# 05_Ethernet.net
KiCad netlist of a schematic drawn in Altium Designer
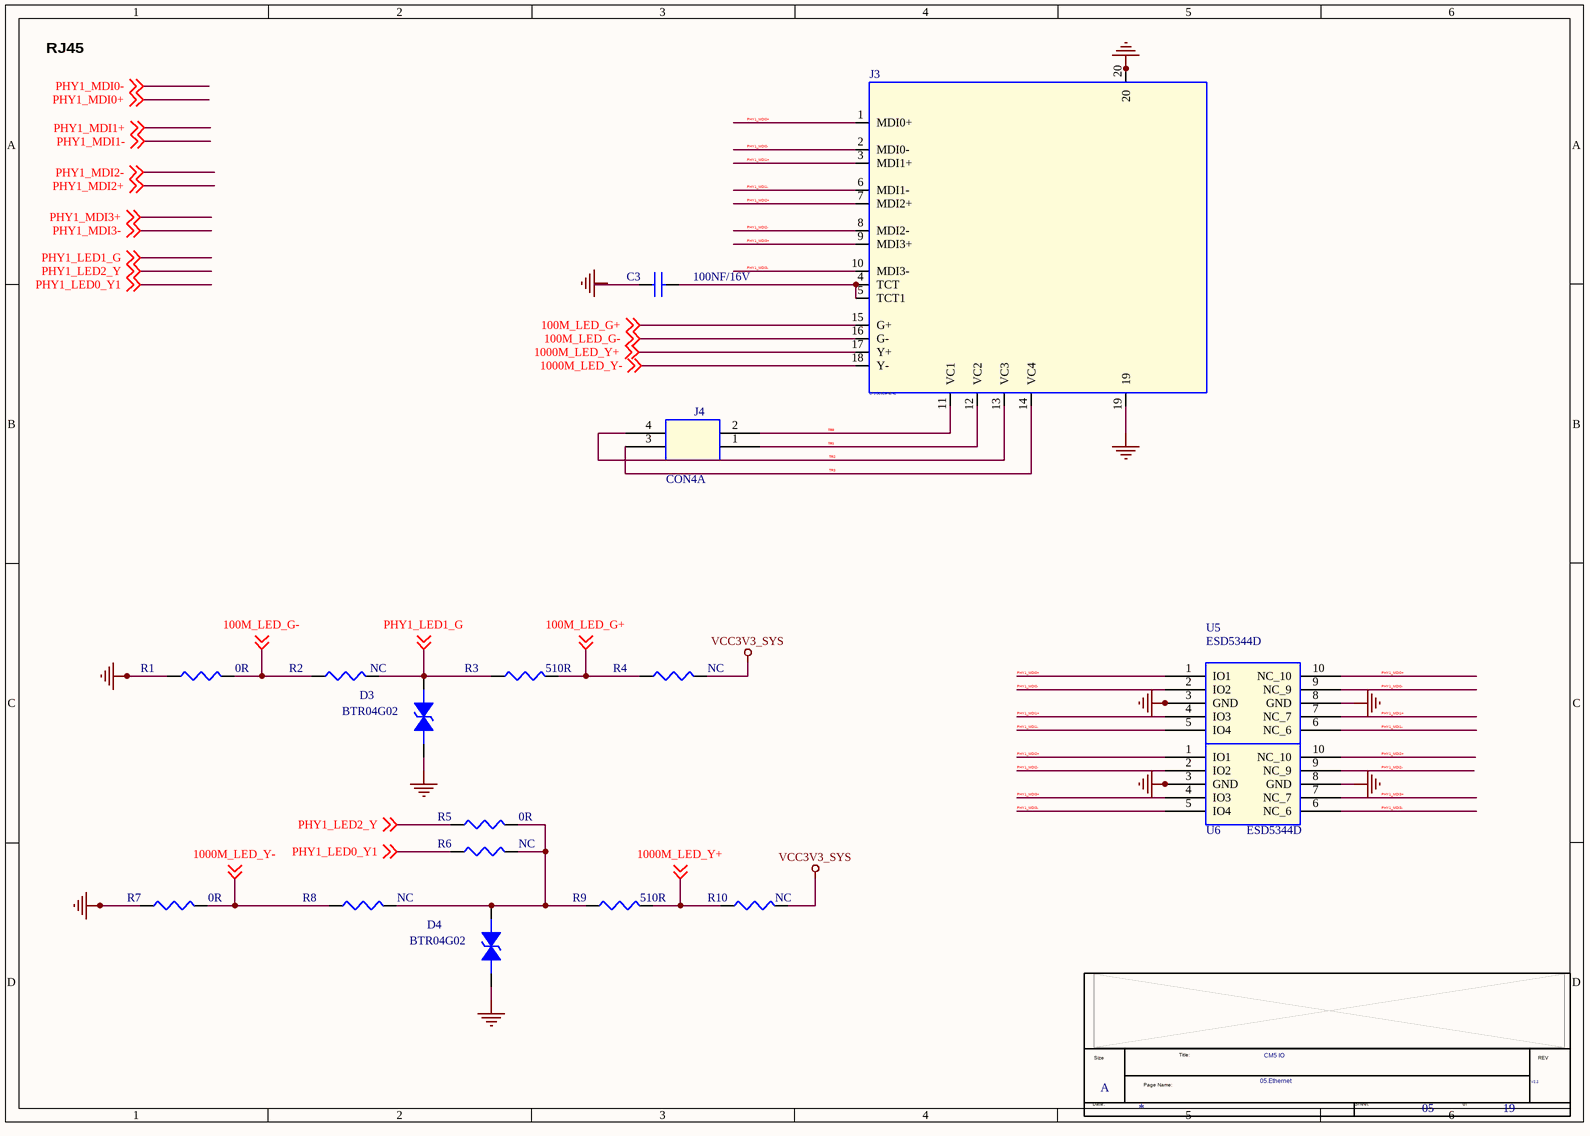
[diagram p0: 05_Ethernet.SchDoc]

(export (version "E")
  (design (tool "Eeschema 10.0.6"))
  (components
    (comp (ref "*")
      (value "radxa_1010")
      (fields
        (field (name "DOC") "05.Ethernet")
        (field (name "REVCODE") "V2.2")
        (field (name "TITLE") "CM5 IO")
        (field (name "PAGE SIZE") "A")
        (field (name "PAGE NUMBER") "05")
        (field (name "PAGE COUNT") "19")
      )
      (libsource (lib "*") (part "radxa_1010"))
    )
    (comp (ref "C3")
      (value "100NF/16V")
      (footprint "C0402")
      (description "cap,100.00nF,+/-10%,16V,X5R,C0402")
      (fields
        (field (name "VOLTAGE") "16V")
        (field (name "TOLERANCE") "10%")
        (field (name "CREATED BY") "JJJ")
      )
      (libsource (lib "*") (part "CAP NP_0"))
    )
    (comp (ref "D3")
      (value "BTR04G02")
      (footprint "ESD0402_1xD5")
      (description "1-Line, Bi-directional, Transient Voltage Suppressors.17.5pF.")
      (fields (field (name "MANUFACTURER") "WillSemi(韦尔半导体)") (field (name "CREATED BY") "JJJ"))
      (libsource (lib "*") (part "DIODE BI_DIR TRIG_2"))
    )
    (comp (ref "D4")
      (value "BTR04G02")
      (footprint "ESD0402_1xD5")
      (description "1-Line, Bi-directional, Transient Voltage Suppressors.17.5pF.")
      (fields (field (name "MANUFACTURER") "WillSemi(韦尔半导体)") (field (name "CREATED BY") "JJJ"))
      (libsource (lib "*") (part "DIODE BI_DIR TRIG_2"))
    )
    (comp (ref "J3")
      (value "LPJG0926HENL")
      (footprint "RJ45_PULSE")
      (description "千兆网口接口，内置变压器")
      (fields (field (name "MANUFACTURER PART NUMBER") "HR911130C") (field (name "CREATED BY") "JJJ"))
      (libsource (lib "*") (part "HR911130C_1"))
    )
    (comp (ref "J4") (value "CON4A") (footprint "DIP4PIN-2_54MM-2X2") (libsource (lib "*") (part "CON4A_0")))
    (comp (ref "R1")
      (value "0R")
      (footprint "R0402")
      (description "通用厚膜电阻,0R,+/-5%,R0402,1/16W.")
      (fields
        (field (name "TOLERANCE") "5%")
        (field (name "MANUFACTURER") "YAGEO")
        (field (name "CREATED BY") "YTL")
      )
      (libsource (lib "*") (part "RESISTOR_0_Dup3"))
    )
    (comp (ref "R2")
      (value "NC")
      (footprint "R0402")
      (description "通用厚膜电阻,0R,+/-5%,R0402,1/16W.")
      (fields
        (field (name "TOLERANCE") "5%")
        (field (name "MANUFACTURER") "YAGEO")
        (field (name "CREATED BY") "YTL")
      )
      (libsource (lib "*") (part "RESISTOR_0_Dup3"))
    )
    (comp (ref "R3")
      (value "510R")
      (footprint "R0402")
      (description "通用厚膜电阻,0R,+/-5%,R0402,1/16W.")
      (fields
        (field (name "TOLERANCE") "5%")
        (field (name "MANUFACTURER") "YAGEO")
        (field (name "CREATED BY") "YTL")
      )
      (libsource (lib "*") (part "RESISTOR_0_Dup3"))
    )
    (comp (ref "R4")
      (value "NC")
      (footprint "R0402")
      (description "通用厚膜电阻,510R,+/-5%,R0402,1/16W.")
      (fields
        (field (name "TOLERANCE") "5%")
        (field (name "MANUFACTURER") "YAGEO")
        (field (name "CREATED BY") "YTL")
      )
      (libsource (lib "*") (part "RESISTOR_0_Dup3"))
    )
    (comp (ref "R5")
      (value "0R")
      (footprint "R0402")
      (description "通用厚膜电阻,0R,+/-5%,R0402,1/16W.")
      (fields
        (field (name "TOLERANCE") "5%")
        (field (name "MANUFACTURER") "YAGEO")
        (field (name "CREATED BY") "YTL")
      )
      (libsource (lib "*") (part "RESISTOR_0_Dup3"))
    )
    (comp (ref "R6")
      (value "NC")
      (footprint "R0402")
      (description "通用厚膜电阻,0R,+/-5%,R0402,1/16W.")
      (fields
        (field (name "TOLERANCE") "5%")
        (field (name "MANUFACTURER") "YAGEO")
        (field (name "CREATED BY") "YTL")
      )
      (libsource (lib "*") (part "RESISTOR_0_Dup3"))
    )
    (comp (ref "R7")
      (value "0R")
      (footprint "R0402")
      (description "通用厚膜电阻,0R,+/-5%,R0402,1/16W.")
      (fields
        (field (name "TOLERANCE") "5%")
        (field (name "MANUFACTURER") "YAGEO")
        (field (name "CREATED BY") "YTL")
      )
      (libsource (lib "*") (part "RESISTOR_0_Dup3"))
    )
    (comp (ref "R8")
      (value "NC")
      (footprint "R0402")
      (description "通用厚膜电阻,0R,+/-5%,R0402,1/16W.")
      (fields
        (field (name "TOLERANCE") "5%")
        (field (name "MANUFACTURER") "YAGEO")
        (field (name "CREATED BY") "YTL")
      )
      (libsource (lib "*") (part "RESISTOR_0_Dup3"))
    )
    (comp (ref "R9")
      (value "510R")
      (footprint "R0402")
      (description "通用厚膜电阻,0R,+/-5%,R0402,1/16W.")
      (fields
        (field (name "TOLERANCE") "5%")
        (field (name "MANUFACTURER") "YAGEO")
        (field (name "CREATED BY") "YTL")
      )
      (libsource (lib "*") (part "RESISTOR_0_Dup3"))
    )
    (comp (ref "R10")
      (value "NC")
      (footprint "R0402")
      (description "通用厚膜电阻,510R,+/-5%,R0402,1/16W.")
      (fields
        (field (name "TOLERANCE") "5%")
        (field (name "MANUFACTURER") "YAGEO")
        (field (name "CREATED BY") "YTL")
      )
      (libsource (lib "*") (part "RESISTOR_0_Dup3"))
    )
    (comp (ref "U5")
      (value "ESD5344D")
      (footprint "SON10_2R50X1R00X0R50")
      (description "4-Lines, Uni-directional, Ultra-low Capacitance Transient Voltage Suppressors")
      (fields (field (name "MANUFACTURER") "WillSemi(韦尔半导体)") (field (name "CREATED BY") "JJJ"))
      (libsource (lib "*") (part "ESD_ESD5304D"))
    )
    (comp (ref "U6")
      (value "ESD5344D")
      (footprint "SON10_2R50X1R00X0R50")
      (description "4-Lines, Uni-directional, Ultra-low Capacitance Transient Voltage Suppressors")
      (fields (field (name "MANUFACTURER") "WillSemi(韦尔半导体)") (field (name "CREATED BY") "JJJ"))
      (libsource (lib "*") (part "ESD_ESD5304D"))
    )
  )
  (nets
    (net (code "1") (name "/TR0") (class "Default")
      (node (ref "J3") (pin "11") (pinfunction "VC1_11") (pintype "passive"))
      (node (ref "J4") (pin "2") (pinfunction "2_2") (pintype "passive"))
    )
    (net (code "2") (name "/TR1") (class "Default")
      (node (ref "J3") (pin "12") (pinfunction "VC2_12") (pintype "passive"))
      (node (ref "J4") (pin "1") (pinfunction "1_1") (pintype "passive"))
    )
    (net (code "3") (name "/TR2") (class "Default")
      (node (ref "J3") (pin "13") (pinfunction "VC3_13") (pintype "passive"))
      (node (ref "J4") (pin "4") (pinfunction "4_4") (pintype "passive"))
    )
    (net (code "4") (name "/TR3") (class "Default")
      (node (ref "J3") (pin "14") (pinfunction "VC4_14") (pintype "passive"))
      (node (ref "J4") (pin "3") (pinfunction "3_3") (pintype "passive"))
    )
    (net (code "5") (name "100M_LED_G+") (class "Default")
      (node (ref "J3") (pin "15") (pinfunction "G+_15") (pintype "passive"))
      (node (ref "R3") (pin "2") (pinfunction "2_2") (pintype "passive"))
      (node (ref "R4") (pin "1") (pinfunction "1_1") (pintype "passive"))
    )
    (net (code "6") (name "100M_LED_G-") (class "Default")
      (node (ref "J3") (pin "16") (pinfunction "G-_16") (pintype "passive"))
      (node (ref "R1") (pin "2") (pinfunction "2_2") (pintype "passive"))
      (node (ref "R2") (pin "1") (pinfunction "1_1") (pintype "passive"))
    )
    (net (code "7") (name "1000M_LED_Y+") (class "Default")
      (node (ref "J3") (pin "17") (pinfunction "Y+_17") (pintype "passive"))
      (node (ref "R10") (pin "1") (pinfunction "1_1") (pintype "passive"))
      (node (ref "R9") (pin "2") (pinfunction "2_2") (pintype "passive"))
    )
    (net (code "8") (name "1000M_LED_Y-") (class "Default")
      (node (ref "J3") (pin "18") (pinfunction "Y-_18") (pintype "passive"))
      (node (ref "R7") (pin "2") (pinfunction "2_2") (pintype "passive"))
      (node (ref "R8") (pin "1") (pinfunction "1_1") (pintype "passive"))
    )
    (net (code "9") (name "GND") (class "Default")
      (node (ref "D3") (pin "1") (pinfunction "1_1") (pintype "passive"))
      (node (ref "D4") (pin "1") (pinfunction "1_1") (pintype "passive"))
      (node (ref "J3") (pin "19") (pinfunction "19_19") (pintype "passive"))
      (node (ref "J3") (pin "20") (pinfunction "20_20") (pintype "passive"))
      (node (ref "R1") (pin "1") (pinfunction "1_1") (pintype "passive"))
      (node (ref "R7") (pin "1") (pinfunction "1_1") (pintype "passive"))
      (node (ref "U5") (pin "3") (pinfunction "GND_3") (pintype "power_in"))
      (node (ref "U5") (pin "8") (pinfunction "GND_8") (pintype "power_in"))
      (node (ref "U6") (pin "3") (pinfunction "GND_3") (pintype "power_in"))
      (node (ref "U6") (pin "8") (pinfunction "GND_8") (pintype "power_in"))
    )
    (net (code "10") (name "Net-(D4-Pad2)") (class "Default")
      (node (ref "D4") (pin "2") (pinfunction "2_2") (pintype "passive"))
      (node (ref "R5") (pin "2") (pinfunction "2_2") (pintype "passive"))
      (node (ref "R6") (pin "2") (pinfunction "2_2") (pintype "passive"))
      (node (ref "R8") (pin "2") (pinfunction "2_2") (pintype "passive"))
      (node (ref "R9") (pin "1") (pinfunction "1_1") (pintype "passive"))
    )
    (net (code "11") (name "Net-(J3-TCT)") (class "Default")
      (node (ref "C3") (pin "2") (pinfunction "2_2") (pintype "passive"))
      (node (ref "J3") (pin "4") (pinfunction "TCT_4") (pintype "passive"))
      (node (ref "J3") (pin "5") (pinfunction "TCT1_5") (pintype "passive"))
    )
    (net (code "12") (name "PHY1_LED0_Y1") (class "Default")
      (node (ref "R6") (pin "1") (pinfunction "1_1") (pintype "passive"))
    )
    (net (code "13") (name "PHY1_LED1_G") (class "Default")
      (node (ref "D3") (pin "2") (pinfunction "2_2") (pintype "passive"))
      (node (ref "R2") (pin "2") (pinfunction "2_2") (pintype "passive"))
      (node (ref "R3") (pin "1") (pinfunction "1_1") (pintype "passive"))
    )
    (net (code "14") (name "PHY1_LED2_Y") (class "Default")
      (node (ref "R5") (pin "1") (pinfunction "1_1") (pintype "passive"))
    )
    (net (code "15") (name "PHY1_MDI0+") (class "Default")
      (node (ref "J3") (pin "1") (pinfunction "MDI0+_1") (pintype "passive"))
      (node (ref "U5") (pin "1") (pinfunction "IO1_1") (pintype "passive"))
      (node (ref "U5") (pin "10") (pinfunction "NC_10_10") (pintype "passive"))
    )
    (net (code "16") (name "PHY1_MDI0-") (class "Default")
      (node (ref "J3") (pin "2") (pinfunction "MDI0-_2") (pintype "passive"))
      (node (ref "U5") (pin "2") (pinfunction "IO2_2") (pintype "passive"))
      (node (ref "U5") (pin "9") (pinfunction "NC_9_9") (pintype "passive"))
    )
    (net (code "17") (name "PHY1_MDI1+") (class "Default")
      (node (ref "J3") (pin "3") (pinfunction "MDI1+_3") (pintype "passive"))
      (node (ref "U5") (pin "4") (pinfunction "IO3_4") (pintype "passive"))
      (node (ref "U5") (pin "7") (pinfunction "NC_7_7") (pintype "passive"))
    )
    (net (code "18") (name "PHY1_MDI1-") (class "Default")
      (node (ref "J3") (pin "6") (pinfunction "MDI1-_6") (pintype "passive"))
      (node (ref "U5") (pin "5") (pinfunction "IO4_5") (pintype "passive"))
      (node (ref "U5") (pin "6") (pinfunction "NC_6_6") (pintype "passive"))
    )
    (net (code "19") (name "PHY1_MDI2+") (class "Default")
      (node (ref "J3") (pin "7") (pinfunction "MDI2+_7") (pintype "passive"))
      (node (ref "U6") (pin "1") (pinfunction "IO1_1") (pintype "passive"))
      (node (ref "U6") (pin "10") (pinfunction "NC_10_10") (pintype "passive"))
    )
    (net (code "20") (name "PHY1_MDI2-") (class "Default")
      (node (ref "J3") (pin "8") (pinfunction "MDI2-_8") (pintype "passive"))
      (node (ref "U6") (pin "2") (pinfunction "IO2_2") (pintype "passive"))
      (node (ref "U6") (pin "9") (pinfunction "NC_9_9") (pintype "passive"))
    )
    (net (code "21") (name "PHY1_MDI3+") (class "Default")
      (node (ref "J3") (pin "9") (pinfunction "MDI3+_9") (pintype "passive"))
      (node (ref "U6") (pin "4") (pinfunction "IO3_4") (pintype "passive"))
      (node (ref "U6") (pin "7") (pinfunction "NC_7_7") (pintype "passive"))
    )
    (net (code "22") (name "PHY1_MDI3-") (class "Default")
      (node (ref "J3") (pin "10") (pinfunction "MDI3-_10") (pintype "passive"))
      (node (ref "U6") (pin "5") (pinfunction "IO4_5") (pintype "passive"))
      (node (ref "U6") (pin "6") (pinfunction "NC_6_6") (pintype "passive"))
    )
    (net (code "23") (name "VCC3V3_SYS") (class "Default")
      (node (ref "R10") (pin "2") (pinfunction "2_2") (pintype "passive"))
      (node (ref "R4") (pin "2") (pinfunction "2_2") (pintype "passive"))
    )
    (net (code "24") (name "unconnected-(C3-Pad1)") (class "Default")
      (node (ref "C3") (pin "1") (pinfunction "1_1") (pintype "passive"))
    )
  )
)
